# 100x75_BOB.net
KiCad netlist of a schematic drawn in EAGLE
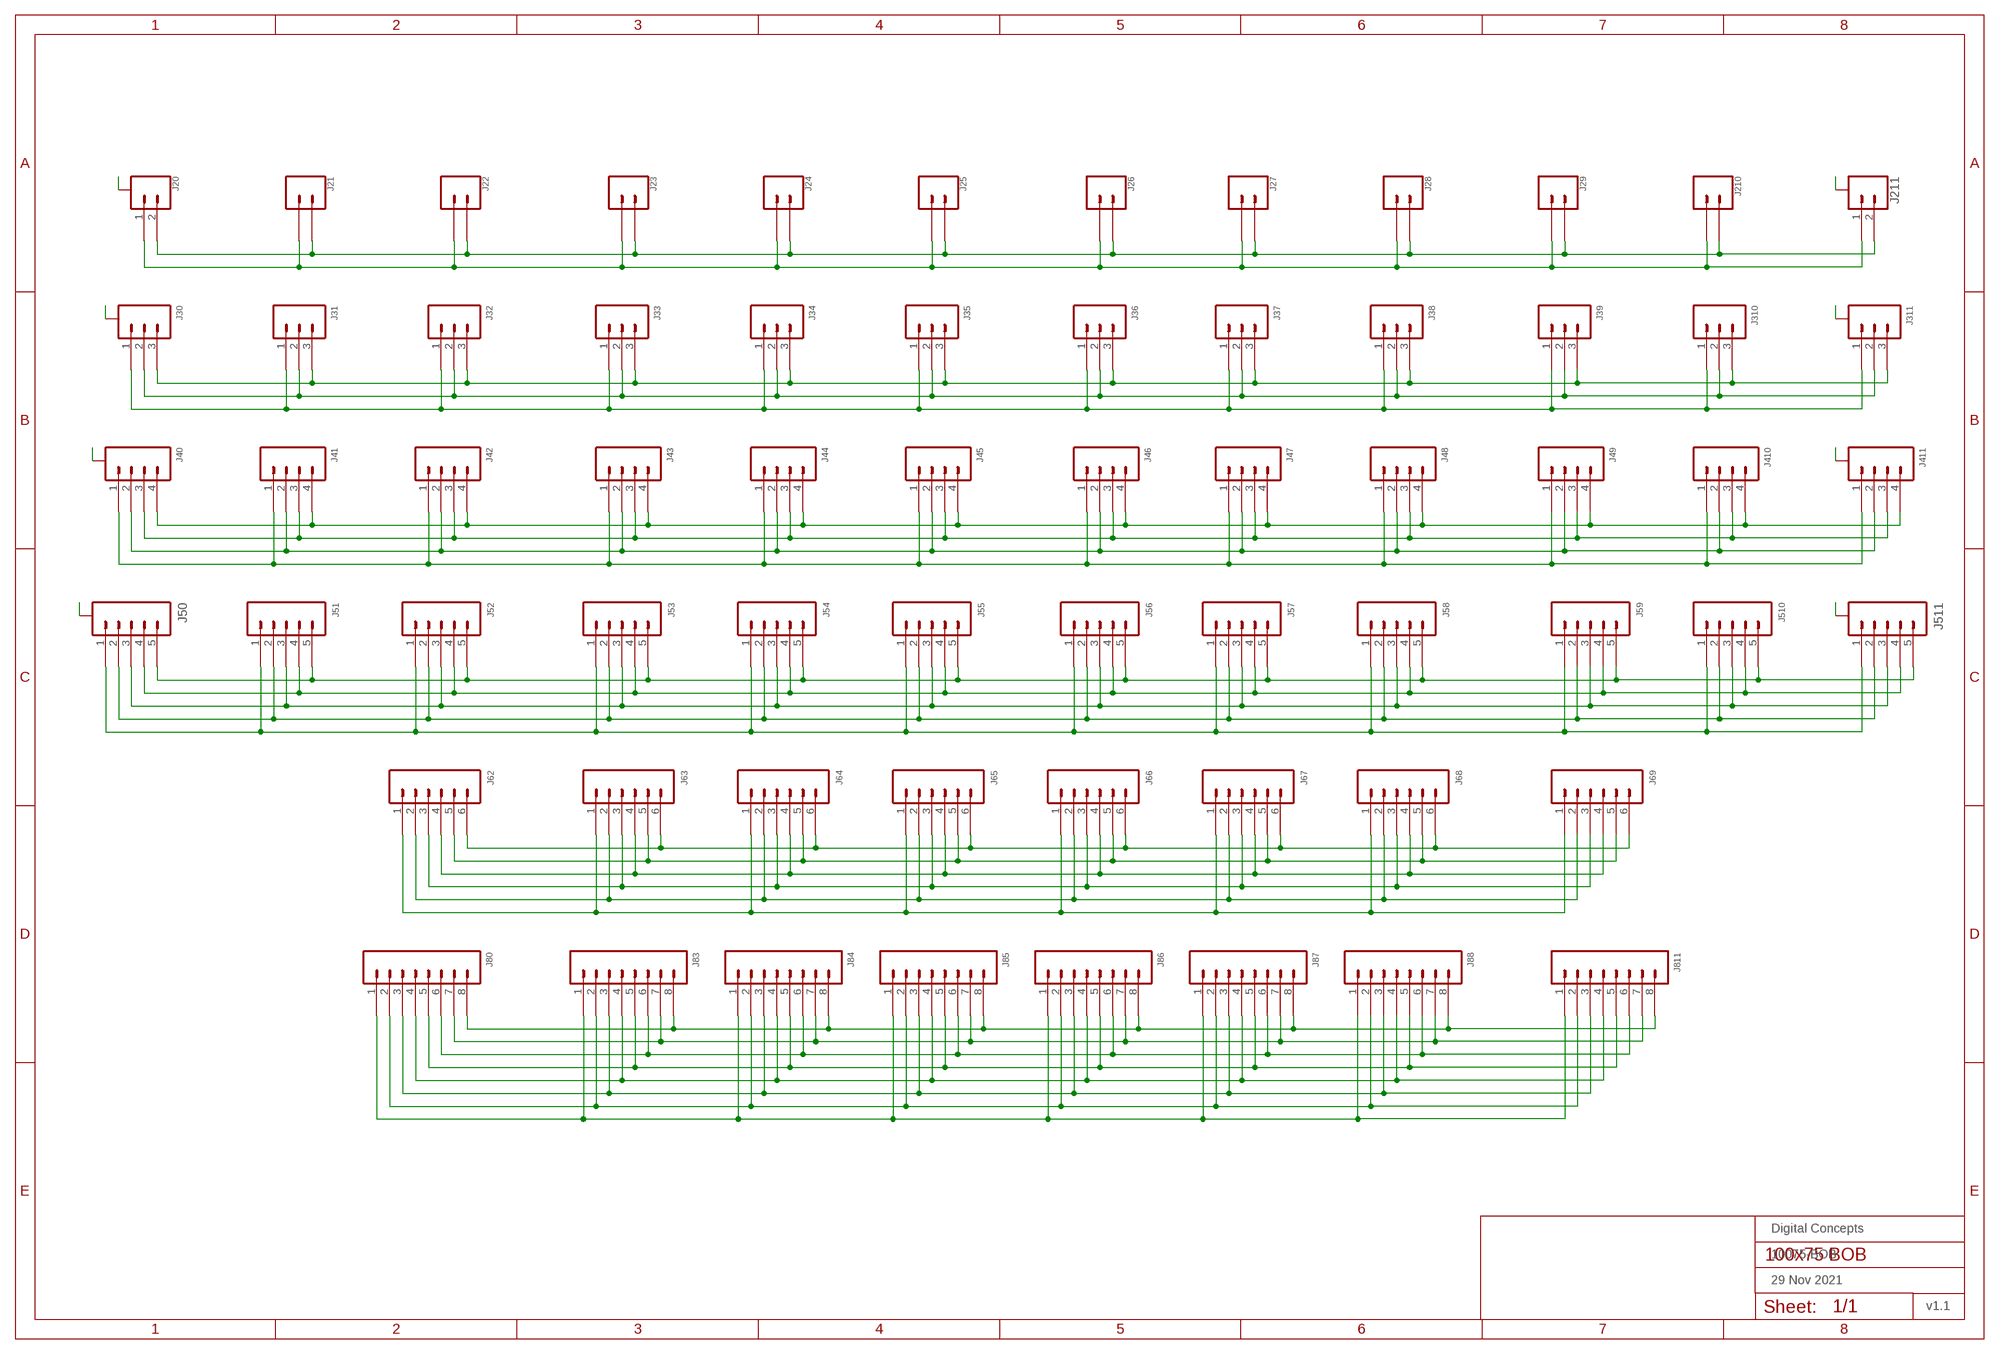
[diagram p0: schematic, sheet 1]

(export (version "E")
  (design (tool "Eeschema 10.0.6"))
  (components
    (comp (ref "J20")
      (value "JST-SH1.0-2-SMD-VERTICAL")
      (footprint "eagle-import:JST-SH1.0-2-VERTICAL")
      (libsource (lib "eagle-import") (part "JST-SH1.0-2-SMD-VERTICAL"))
    )
    (comp (ref "J21")
      (value "JST-GH1.25-2-VERTICAL")
      (footprint "eagle-import:JST-GH1.25-2-VERTICAL")
      (libsource (lib "eagle-import") (part "JST-GH1.25-2-VERTICAL"))
    )
    (comp (ref "J22")
      (value "JST-PH2.0-2-VERTICAL")
      (footprint "eagle-import:JST-PH2.0-2-VERTICAL")
      (libsource (lib "eagle-import") (part "JST-PH2.0-2-VERTICAL"))
    )
    (comp (ref "J23")
      (value "HEADER-1X2-GENERIC")
      (footprint "eagle-import:CONN_02-GENERIC")
      (libsource (lib "eagle-import") (part "HEADER-1X2-GENERIC"))
    )
    (comp (ref "J24")
      (value "HEADER-1X2-GENERIC")
      (footprint "eagle-import:CONN_02-GENERIC")
      (libsource (lib "eagle-import") (part "HEADER-1X2-GENERIC"))
    )
    (comp (ref "J25")
      (value "HEADER-1X2-GENERIC")
      (footprint "eagle-import:CONN_02-GENERIC")
      (libsource (lib "eagle-import") (part "HEADER-1X2-GENERIC"))
    )
    (comp (ref "J26")
      (value "HEADER-1X2-GENERIC")
      (footprint "eagle-import:CONN_02-GENERIC")
      (libsource (lib "eagle-import") (part "HEADER-1X2-GENERIC"))
    )
    (comp (ref "J27")
      (value "HEADER-1X2-GENERIC")
      (footprint "eagle-import:CONN_02-GENERIC")
      (libsource (lib "eagle-import") (part "HEADER-1X2-GENERIC"))
    )
    (comp (ref "J28")
      (value "HEADER-1X2-GENERIC")
      (footprint "eagle-import:CONN_02-GENERIC")
      (libsource (lib "eagle-import") (part "HEADER-1X2-GENERIC"))
    )
    (comp (ref "J29")
      (value "JST-PH2.0-2-VERTICAL")
      (footprint "eagle-import:JST-PH2.0-2-VERTICAL")
      (libsource (lib "eagle-import") (part "JST-PH2.0-2-VERTICAL"))
    )
    (comp (ref "J30")
      (value "JST-SH1.0-3-SMD-VERTICAL")
      (footprint "eagle-import:JST-SH1.0-3-VERTICAL")
      (libsource (lib "eagle-import") (part "JST-SH1.0-3-SMD-VERTICAL"))
    )
    (comp (ref "J31")
      (value "JST-GH1.25-3-VERTICAL")
      (footprint "eagle-import:JST-GH1.25-3-VERTICAL")
      (libsource (lib "eagle-import") (part "JST-GH1.25-3-VERTICAL"))
    )
    (comp (ref "J32")
      (value "JST-PH2.0-3-VERTICAL")
      (footprint "eagle-import:JST-PH2.0-3-VERTICAL")
      (libsource (lib "eagle-import") (part "JST-PH2.0-3-VERTICAL"))
    )
    (comp (ref "J33")
      (value "HEADER-1X3-GENERIC")
      (footprint "eagle-import:CONN_03-GENERIC")
      (libsource (lib "eagle-import") (part "HEADER-1X3-GENERIC"))
    )
    (comp (ref "J34")
      (value "HEADER-1X3-GENERIC")
      (footprint "eagle-import:CONN_03-GENERIC")
      (libsource (lib "eagle-import") (part "HEADER-1X3-GENERIC"))
    )
    (comp (ref "J35")
      (value "HEADER-1X3-GENERIC")
      (footprint "eagle-import:CONN_03-GENERIC")
      (libsource (lib "eagle-import") (part "HEADER-1X3-GENERIC"))
    )
    (comp (ref "J36")
      (value "HEADER-1X3-GENERIC")
      (footprint "eagle-import:CONN_03-GENERIC")
      (libsource (lib "eagle-import") (part "HEADER-1X3-GENERIC"))
    )
    (comp (ref "J37")
      (value "HEADER-1X3-GENERIC")
      (footprint "eagle-import:CONN_03-GENERIC")
      (libsource (lib "eagle-import") (part "HEADER-1X3-GENERIC"))
    )
    (comp (ref "J38")
      (value "HEADER-1X3-GENERIC")
      (footprint "eagle-import:CONN_03-GENERIC")
      (libsource (lib "eagle-import") (part "HEADER-1X3-GENERIC"))
    )
    (comp (ref "J39")
      (value "JST-PH2.0-3-VERTICAL")
      (footprint "eagle-import:JST-PH2.0-3-VERTICAL")
      (libsource (lib "eagle-import") (part "JST-PH2.0-3-VERTICAL"))
    )
    (comp (ref "J40")
      (value "JST-SH1.0-4-SMD-VERTICAL")
      (footprint "eagle-import:JST-SH1.0-4-VERTICAL")
      (libsource (lib "eagle-import") (part "JST-SH1.0-4-SMD-VERTICAL"))
    )
    (comp (ref "J41")
      (value "JST-GH1.25-4-VERTICAL")
      (footprint "eagle-import:JST-GH1.25-4-VERTICAL")
      (libsource (lib "eagle-import") (part "JST-GH1.25-4-VERTICAL"))
    )
    (comp (ref "J42")
      (value "JST-PH2.0-4-VERTICAL")
      (footprint "eagle-import:JST-PH2.0-4-VERTICAL")
      (libsource (lib "eagle-import") (part "JST-PH2.0-4-VERTICAL"))
    )
    (comp (ref "J43")
      (value "HEADER-1X4-GENERIC")
      (footprint "eagle-import:CONN_04-GENERIC")
      (libsource (lib "eagle-import") (part "HEADER-1X4-GENERIC"))
    )
    (comp (ref "J44")
      (value "HEADER-1X4-GENERIC")
      (footprint "eagle-import:CONN_04-GENERIC")
      (libsource (lib "eagle-import") (part "HEADER-1X4-GENERIC"))
    )
    (comp (ref "J45")
      (value "HEADER-1X4-GENERIC")
      (footprint "eagle-import:CONN_04-GENERIC")
      (libsource (lib "eagle-import") (part "HEADER-1X4-GENERIC"))
    )
    (comp (ref "J46")
      (value "HEADER-1X4-GENERIC")
      (footprint "eagle-import:CONN_04-GENERIC")
      (libsource (lib "eagle-import") (part "HEADER-1X4-GENERIC"))
    )
    (comp (ref "J47")
      (value "HEADER-1X4-GENERIC")
      (footprint "eagle-import:CONN_04-GENERIC")
      (libsource (lib "eagle-import") (part "HEADER-1X4-GENERIC"))
    )
    (comp (ref "J48")
      (value "HEADER-1X4-GENERIC")
      (footprint "eagle-import:CONN_04-GENERIC")
      (libsource (lib "eagle-import") (part "HEADER-1X4-GENERIC"))
    )
    (comp (ref "J49")
      (value "JST-PH2.0-4-VERTICAL")
      (footprint "eagle-import:JST-PH2.0-4-VERTICAL")
      (libsource (lib "eagle-import") (part "JST-PH2.0-4-VERTICAL"))
    )
    (comp (ref "J50")
      (value "JST-SH1.0-5-SMD-VERTICAL")
      (footprint "eagle-import:JST-SH1.0-5-VERTICAL")
      (libsource (lib "eagle-import") (part "JST-SH1.0-5-SMD-VERTICAL"))
    )
    (comp (ref "J51")
      (value "JST-GH1.25-5-VERTICAL")
      (footprint "eagle-import:JST-GH1.25-5-VERTICAL")
      (libsource (lib "eagle-import") (part "JST-GH1.25-5-VERTICAL"))
    )
    (comp (ref "J52")
      (value "JST-PH2.0-5-VERTICAL")
      (footprint "eagle-import:JST-PH2.0-5-VERTICAL")
      (libsource (lib "eagle-import") (part "JST-PH2.0-5-VERTICAL"))
    )
    (comp (ref "J53")
      (value "HEADER-1X5-GENERIC")
      (footprint "eagle-import:CONN_05-GENERIC")
      (libsource (lib "eagle-import") (part "HEADER-1X5-GENERIC"))
    )
    (comp (ref "J54")
      (value "HEADER-1X5-GENERIC")
      (footprint "eagle-import:CONN_05-GENERIC")
      (libsource (lib "eagle-import") (part "HEADER-1X5-GENERIC"))
    )
    (comp (ref "J55")
      (value "HEADER-1X5-GENERIC")
      (footprint "eagle-import:CONN_05-GENERIC")
      (libsource (lib "eagle-import") (part "HEADER-1X5-GENERIC"))
    )
    (comp (ref "J56")
      (value "HEADER-1X5-GENERIC")
      (footprint "eagle-import:CONN_05-GENERIC")
      (libsource (lib "eagle-import") (part "HEADER-1X5-GENERIC"))
    )
    (comp (ref "J57")
      (value "HEADER-1X5-GENERIC")
      (footprint "eagle-import:CONN_05-GENERIC")
      (libsource (lib "eagle-import") (part "HEADER-1X5-GENERIC"))
    )
    (comp (ref "J58")
      (value "HEADER-1X5-GENERIC")
      (footprint "eagle-import:CONN_05-GENERIC")
      (libsource (lib "eagle-import") (part "HEADER-1X5-GENERIC"))
    )
    (comp (ref "J59")
      (value "JST-PH2.0-5-VERTICAL")
      (footprint "eagle-import:JST-PH2.0-5-VERTICAL")
      (libsource (lib "eagle-import") (part "JST-PH2.0-5-VERTICAL"))
    )
    (comp (ref "J62")
      (value "RJ11-6P6C-VERTICAL")
      (footprint "eagle-import:RJ11-6-VERTICAL")
      (libsource (lib "eagle-import") (part "RJ11-6P6C-VERTICAL"))
    )
    (comp (ref "J63")
      (value "HEADER-1X6-GENERIC")
      (footprint "eagle-import:CONN_06-GENERIC")
      (libsource (lib "eagle-import") (part "HEADER-1X6-GENERIC"))
    )
    (comp (ref "J64")
      (value "HEADER-1X6-GENERIC")
      (footprint "eagle-import:CONN_06-GENERIC")
      (libsource (lib "eagle-import") (part "HEADER-1X6-GENERIC"))
    )
    (comp (ref "J65")
      (value "HEADER-1X6-GENERIC")
      (footprint "eagle-import:CONN_06-GENERIC")
      (libsource (lib "eagle-import") (part "HEADER-1X6-GENERIC"))
    )
    (comp (ref "J66")
      (value "HEADER-1X6-GENERIC")
      (footprint "eagle-import:CONN_06-GENERIC")
      (libsource (lib "eagle-import") (part "HEADER-1X6-GENERIC"))
    )
    (comp (ref "J67")
      (value "HEADER-1X6-GENERIC")
      (footprint "eagle-import:CONN_06-GENERIC")
      (libsource (lib "eagle-import") (part "HEADER-1X6-GENERIC"))
    )
    (comp (ref "J68")
      (value "HEADER-1X6-GENERIC")
      (footprint "eagle-import:CONN_06-GENERIC")
      (libsource (lib "eagle-import") (part "HEADER-1X6-GENERIC"))
    )
    (comp (ref "J69")
      (value "RJ11-6P6C-VERTICAL")
      (footprint "eagle-import:RJ11-6-VERTICAL")
      (libsource (lib "eagle-import") (part "RJ11-6P6C-VERTICAL"))
    )
    (comp (ref "J80")
      (value "RJ45-8P8C-VERTICAL-MK2")
      (footprint "eagle-import:RJ45-VERTICAL-MK2")
      (libsource (lib "eagle-import") (part "RJ45-8P8C-VERTICAL-MK2"))
    )
    (comp (ref "J83")
      (value "HEADER-1X8-GENERIC")
      (footprint "eagle-import:CONN_08-GENERIC")
      (libsource (lib "eagle-import") (part "HEADER-1X8-GENERIC"))
    )
    (comp (ref "J84")
      (value "HEADER-1X8-GENERIC")
      (footprint "eagle-import:CONN_08-GENERIC")
      (libsource (lib "eagle-import") (part "HEADER-1X8-GENERIC"))
    )
    (comp (ref "J85")
      (value "HEADER-1X8-GENERIC")
      (footprint "eagle-import:CONN_08-GENERIC")
      (libsource (lib "eagle-import") (part "HEADER-1X8-GENERIC"))
    )
    (comp (ref "J86")
      (value "HEADER-1X8-GENERIC")
      (footprint "eagle-import:CONN_08-GENERIC")
      (libsource (lib "eagle-import") (part "HEADER-1X8-GENERIC"))
    )
    (comp (ref "J87")
      (value "HEADER-1X8-GENERIC")
      (footprint "eagle-import:CONN_08-GENERIC")
      (libsource (lib "eagle-import") (part "HEADER-1X8-GENERIC"))
    )
    (comp (ref "J88")
      (value "HEADER-1X8-GENERIC")
      (footprint "eagle-import:CONN_08-GENERIC")
      (libsource (lib "eagle-import") (part "HEADER-1X8-GENERIC"))
    )
    (comp (ref "J210")
      (value "JST-GH1.25-2-VERTICAL")
      (footprint "eagle-import:JST-GH1.25-2-VERTICAL")
      (libsource (lib "eagle-import") (part "JST-GH1.25-2-VERTICAL"))
    )
    (comp (ref "J211")
      (value "JST-SH1.0-2-SMD-VERTICAL")
      (footprint "eagle-import:JST-SH1.0-2-VERTICAL")
      (libsource (lib "eagle-import") (part "JST-SH1.0-2-SMD-VERTICAL"))
    )
    (comp (ref "J310")
      (value "JST-GH1.25-3-VERTICAL")
      (footprint "eagle-import:JST-GH1.25-3-VERTICAL")
      (libsource (lib "eagle-import") (part "JST-GH1.25-3-VERTICAL"))
    )
    (comp (ref "J311")
      (value "JST-SH1.0-3-SMD-VERTICAL")
      (footprint "eagle-import:JST-SH1.0-3-VERTICAL")
      (libsource (lib "eagle-import") (part "JST-SH1.0-3-SMD-VERTICAL"))
    )
    (comp (ref "J410")
      (value "JST-GH1.25-4-VERTICAL")
      (footprint "eagle-import:JST-GH1.25-4-VERTICAL")
      (libsource (lib "eagle-import") (part "JST-GH1.25-4-VERTICAL"))
    )
    (comp (ref "J411")
      (value "JST-SH1.0-4-SMD-VERTICAL")
      (footprint "eagle-import:JST-SH1.0-4-VERTICAL")
      (libsource (lib "eagle-import") (part "JST-SH1.0-4-SMD-VERTICAL"))
    )
    (comp (ref "J510")
      (value "JST-GH1.25-5-VERTICAL")
      (footprint "eagle-import:JST-GH1.25-5-VERTICAL")
      (libsource (lib "eagle-import") (part "JST-GH1.25-5-VERTICAL"))
    )
    (comp (ref "J511")
      (value "JST-SH1.0-5-SMD-VERTICAL")
      (footprint "eagle-import:JST-SH1.0-5-VERTICAL")
      (libsource (lib "eagle-import") (part "JST-SH1.0-5-SMD-VERTICAL"))
    )
    (comp (ref "J811")
      (value "RJ45-8P8C-VERTICAL-MK2")
      (footprint "eagle-import:RJ45-VERTICAL-MK2")
      (libsource (lib "eagle-import") (part "RJ45-8P8C-VERTICAL-MK2"))
    )
  )
  (nets
    (net (code "1") (name "/A") (class "Default")
      (node (ref "J20") (pin "A@1") (pinfunction "A_A@1") (pintype "power_in"))
      (node (ref "J20") (pin "A@2") (pinfunction "A_A@2") (pintype "power_in"))
      (node (ref "J211") (pin "A@1") (pinfunction "A_A@1") (pintype "power_in"))
      (node (ref "J211") (pin "A@2") (pinfunction "A_A@2") (pintype "power_in"))
      (node (ref "J30") (pin "A@1") (pinfunction "A_A@1") (pintype "power_in"))
      (node (ref "J30") (pin "A@3") (pinfunction "A_A@3") (pintype "power_in"))
      (node (ref "J311") (pin "A@1") (pinfunction "A_A@1") (pintype "power_in"))
      (node (ref "J311") (pin "A@3") (pinfunction "A_A@3") (pintype "power_in"))
      (node (ref "J40") (pin "A@1") (pinfunction "A_A@1") (pintype "power_in"))
      (node (ref "J40") (pin "A@4") (pinfunction "A_A@4") (pintype "power_in"))
      (node (ref "J411") (pin "A@1") (pinfunction "A_A@1") (pintype "power_in"))
      (node (ref "J411") (pin "A@4") (pinfunction "A_A@4") (pintype "power_in"))
      (node (ref "J50") (pin "A@1") (pinfunction "A_A@1") (pintype "power_in"))
      (node (ref "J50") (pin "A@5") (pinfunction "A_A@5") (pintype "power_in"))
      (node (ref "J511") (pin "A@1") (pinfunction "A_A@1") (pintype "power_in"))
      (node (ref "J511") (pin "A@5") (pinfunction "A_A@5") (pintype "power_in"))
    )
    (net (code "2") (name "Net-(J20-Pad1)") (class "Default")
      (node (ref "J20") (pin "1") (pinfunction "1_1") (pintype "passive"))
      (node (ref "J21") (pin "1") (pinfunction "1_1") (pintype "passive"))
      (node (ref "J210") (pin "1") (pinfunction "1_1") (pintype "passive"))
      (node (ref "J211") (pin "1") (pinfunction "1_1") (pintype "passive"))
      (node (ref "J22") (pin "1") (pinfunction "1_1") (pintype "passive"))
      (node (ref "J23") (pin "1") (pinfunction "1_1") (pintype "passive"))
      (node (ref "J24") (pin "1") (pinfunction "1_1") (pintype "passive"))
      (node (ref "J25") (pin "1") (pinfunction "1_1") (pintype "passive"))
      (node (ref "J26") (pin "1") (pinfunction "1_1") (pintype "passive"))
      (node (ref "J27") (pin "1") (pinfunction "1_1") (pintype "passive"))
      (node (ref "J28") (pin "1") (pinfunction "1_1") (pintype "passive"))
      (node (ref "J29") (pin "1") (pinfunction "1_1") (pintype "passive"))
    )
    (net (code "3") (name "Net-(J20-Pad2)") (class "Default")
      (node (ref "J20") (pin "2") (pinfunction "2_2") (pintype "passive"))
      (node (ref "J21") (pin "2") (pinfunction "2_2") (pintype "passive"))
      (node (ref "J210") (pin "2") (pinfunction "2_2") (pintype "passive"))
      (node (ref "J211") (pin "2") (pinfunction "2_2") (pintype "passive"))
      (node (ref "J22") (pin "2") (pinfunction "2_2") (pintype "passive"))
      (node (ref "J23") (pin "2") (pinfunction "2_2") (pintype "passive"))
      (node (ref "J24") (pin "2") (pinfunction "2_2") (pintype "passive"))
      (node (ref "J25") (pin "2") (pinfunction "2_2") (pintype "passive"))
      (node (ref "J26") (pin "2") (pinfunction "2_2") (pintype "passive"))
      (node (ref "J27") (pin "2") (pinfunction "2_2") (pintype "passive"))
      (node (ref "J28") (pin "2") (pinfunction "2_2") (pintype "passive"))
      (node (ref "J29") (pin "2") (pinfunction "2_2") (pintype "passive"))
    )
    (net (code "4") (name "Net-(J30-Pad1)") (class "Default")
      (node (ref "J30") (pin "1") (pinfunction "1_1") (pintype "passive"))
      (node (ref "J31") (pin "1") (pinfunction "1_1") (pintype "passive"))
      (node (ref "J310") (pin "1") (pinfunction "1_1") (pintype "passive"))
      (node (ref "J311") (pin "1") (pinfunction "1_1") (pintype "passive"))
      (node (ref "J32") (pin "1") (pinfunction "1_1") (pintype "passive"))
      (node (ref "J33") (pin "1") (pinfunction "1_1") (pintype "passive"))
      (node (ref "J34") (pin "1") (pinfunction "1_1") (pintype "passive"))
      (node (ref "J35") (pin "1") (pinfunction "1_1") (pintype "passive"))
      (node (ref "J36") (pin "1") (pinfunction "1_1") (pintype "passive"))
      (node (ref "J37") (pin "1") (pinfunction "1_1") (pintype "passive"))
      (node (ref "J38") (pin "1") (pinfunction "1_1") (pintype "passive"))
      (node (ref "J39") (pin "1") (pinfunction "1_1") (pintype "passive"))
    )
    (net (code "5") (name "Net-(J30-Pad2)") (class "Default")
      (node (ref "J30") (pin "2") (pinfunction "2_2") (pintype "passive"))
      (node (ref "J31") (pin "2") (pinfunction "2_2") (pintype "passive"))
      (node (ref "J310") (pin "2") (pinfunction "2_2") (pintype "passive"))
      (node (ref "J311") (pin "2") (pinfunction "2_2") (pintype "passive"))
      (node (ref "J32") (pin "2") (pinfunction "2_2") (pintype "passive"))
      (node (ref "J33") (pin "2") (pinfunction "2_2") (pintype "passive"))
      (node (ref "J34") (pin "2") (pinfunction "2_2") (pintype "passive"))
      (node (ref "J35") (pin "2") (pinfunction "2_2") (pintype "passive"))
      (node (ref "J36") (pin "2") (pinfunction "2_2") (pintype "passive"))
      (node (ref "J37") (pin "2") (pinfunction "2_2") (pintype "passive"))
      (node (ref "J38") (pin "2") (pinfunction "2_2") (pintype "passive"))
      (node (ref "J39") (pin "2") (pinfunction "2_2") (pintype "passive"))
    )
    (net (code "6") (name "Net-(J30-Pad3)") (class "Default")
      (node (ref "J30") (pin "3") (pinfunction "3_3") (pintype "passive"))
      (node (ref "J31") (pin "3") (pinfunction "3_3") (pintype "passive"))
      (node (ref "J310") (pin "3") (pinfunction "3_3") (pintype "passive"))
      (node (ref "J311") (pin "3") (pinfunction "3_3") (pintype "passive"))
      (node (ref "J32") (pin "3") (pinfunction "3_3") (pintype "passive"))
      (node (ref "J33") (pin "3") (pinfunction "3_3") (pintype "passive"))
      (node (ref "J34") (pin "3") (pinfunction "3_3") (pintype "passive"))
      (node (ref "J35") (pin "3") (pinfunction "3_3") (pintype "passive"))
      (node (ref "J36") (pin "3") (pinfunction "3_3") (pintype "passive"))
      (node (ref "J37") (pin "3") (pinfunction "3_3") (pintype "passive"))
      (node (ref "J38") (pin "3") (pinfunction "3_3") (pintype "passive"))
      (node (ref "J39") (pin "3") (pinfunction "3_3") (pintype "passive"))
    )
    (net (code "7") (name "Net-(J40-Pad1)") (class "Default")
      (node (ref "J40") (pin "1") (pinfunction "1_1") (pintype "passive"))
      (node (ref "J41") (pin "1") (pinfunction "1_1") (pintype "passive"))
      (node (ref "J410") (pin "1") (pinfunction "1_1") (pintype "passive"))
      (node (ref "J411") (pin "1") (pinfunction "1_1") (pintype "passive"))
      (node (ref "J42") (pin "1") (pinfunction "1_1") (pintype "passive"))
      (node (ref "J43") (pin "1") (pinfunction "1_1") (pintype "passive"))
      (node (ref "J44") (pin "1") (pinfunction "1_1") (pintype "passive"))
      (node (ref "J45") (pin "1") (pinfunction "1_1") (pintype "passive"))
      (node (ref "J46") (pin "1") (pinfunction "1_1") (pintype "passive"))
      (node (ref "J47") (pin "1") (pinfunction "1_1") (pintype "passive"))
      (node (ref "J48") (pin "1") (pinfunction "1_1") (pintype "passive"))
      (node (ref "J49") (pin "1") (pinfunction "1_1") (pintype "passive"))
    )
    (net (code "8") (name "Net-(J40-Pad2)") (class "Default")
      (node (ref "J40") (pin "2") (pinfunction "2_2") (pintype "passive"))
      (node (ref "J41") (pin "2") (pinfunction "2_2") (pintype "passive"))
      (node (ref "J410") (pin "2") (pinfunction "2_2") (pintype "passive"))
      (node (ref "J411") (pin "2") (pinfunction "2_2") (pintype "passive"))
      (node (ref "J42") (pin "2") (pinfunction "2_2") (pintype "passive"))
      (node (ref "J43") (pin "2") (pinfunction "2_2") (pintype "passive"))
      (node (ref "J44") (pin "2") (pinfunction "2_2") (pintype "passive"))
      (node (ref "J45") (pin "2") (pinfunction "2_2") (pintype "passive"))
      (node (ref "J46") (pin "2") (pinfunction "2_2") (pintype "passive"))
      (node (ref "J47") (pin "2") (pinfunction "2_2") (pintype "passive"))
      (node (ref "J48") (pin "2") (pinfunction "2_2") (pintype "passive"))
      (node (ref "J49") (pin "2") (pinfunction "2_2") (pintype "passive"))
    )
    (net (code "9") (name "Net-(J40-Pad3)") (class "Default")
      (node (ref "J40") (pin "3") (pinfunction "3_3") (pintype "passive"))
      (node (ref "J41") (pin "3") (pinfunction "3_3") (pintype "passive"))
      (node (ref "J410") (pin "3") (pinfunction "3_3") (pintype "passive"))
      (node (ref "J411") (pin "3") (pinfunction "3_3") (pintype "passive"))
      (node (ref "J42") (pin "3") (pinfunction "3_3") (pintype "passive"))
      (node (ref "J43") (pin "3") (pinfunction "3_3") (pintype "passive"))
      (node (ref "J44") (pin "3") (pinfunction "3_3") (pintype "passive"))
      (node (ref "J45") (pin "3") (pinfunction "3_3") (pintype "passive"))
      (node (ref "J46") (pin "3") (pinfunction "3_3") (pintype "passive"))
      (node (ref "J47") (pin "3") (pinfunction "3_3") (pintype "passive"))
      (node (ref "J48") (pin "3") (pinfunction "3_3") (pintype "passive"))
      (node (ref "J49") (pin "3") (pinfunction "3_3") (pintype "passive"))
    )
    (net (code "10") (name "Net-(J40-Pad4)") (class "Default")
      (node (ref "J40") (pin "4") (pinfunction "4_4") (pintype "passive"))
      (node (ref "J41") (pin "4") (pinfunction "4_4") (pintype "passive"))
      (node (ref "J410") (pin "4") (pinfunction "4_4") (pintype "passive"))
      (node (ref "J411") (pin "4") (pinfunction "4_4") (pintype "passive"))
      (node (ref "J42") (pin "4") (pinfunction "4_4") (pintype "passive"))
      (node (ref "J43") (pin "4") (pinfunction "4_4") (pintype "passive"))
      (node (ref "J44") (pin "4") (pinfunction "4_4") (pintype "passive"))
      (node (ref "J45") (pin "4") (pinfunction "4_4") (pintype "passive"))
      (node (ref "J46") (pin "4") (pinfunction "4_4") (pintype "passive"))
      (node (ref "J47") (pin "4") (pinfunction "4_4") (pintype "passive"))
      (node (ref "J48") (pin "4") (pinfunction "4_4") (pintype "passive"))
      (node (ref "J49") (pin "4") (pinfunction "4_4") (pintype "passive"))
    )
    (net (code "11") (name "Net-(J50-Pad1)") (class "Default")
      (node (ref "J50") (pin "1") (pinfunction "1_1") (pintype "passive"))
      (node (ref "J51") (pin "1") (pinfunction "1_1") (pintype "passive"))
      (node (ref "J510") (pin "1") (pinfunction "1_1") (pintype "passive"))
      (node (ref "J511") (pin "1") (pinfunction "1_1") (pintype "passive"))
      (node (ref "J52") (pin "1") (pinfunction "1_1") (pintype "passive"))
      (node (ref "J53") (pin "1") (pinfunction "1_1") (pintype "passive"))
      (node (ref "J54") (pin "1") (pinfunction "1_1") (pintype "passive"))
      (node (ref "J55") (pin "1") (pinfunction "1_1") (pintype "passive"))
      (node (ref "J56") (pin "1") (pinfunction "1_1") (pintype "passive"))
      (node (ref "J57") (pin "1") (pinfunction "1_1") (pintype "passive"))
      (node (ref "J58") (pin "1") (pinfunction "1_1") (pintype "passive"))
      (node (ref "J59") (pin "1") (pinfunction "1_1") (pintype "passive"))
    )
    (net (code "12") (name "Net-(J50-Pad2)") (class "Default")
      (node (ref "J50") (pin "2") (pinfunction "2_2") (pintype "passive"))
      (node (ref "J51") (pin "2") (pinfunction "2_2") (pintype "passive"))
      (node (ref "J510") (pin "2") (pinfunction "2_2") (pintype "passive"))
      (node (ref "J511") (pin "2") (pinfunction "2_2") (pintype "passive"))
      (node (ref "J52") (pin "2") (pinfunction "2_2") (pintype "passive"))
      (node (ref "J53") (pin "2") (pinfunction "2_2") (pintype "passive"))
      (node (ref "J54") (pin "2") (pinfunction "2_2") (pintype "passive"))
      (node (ref "J55") (pin "2") (pinfunction "2_2") (pintype "passive"))
      (node (ref "J56") (pin "2") (pinfunction "2_2") (pintype "passive"))
      (node (ref "J57") (pin "2") (pinfunction "2_2") (pintype "passive"))
      (node (ref "J58") (pin "2") (pinfunction "2_2") (pintype "passive"))
      (node (ref "J59") (pin "2") (pinfunction "2_2") (pintype "passive"))
    )
    (net (code "13") (name "Net-(J50-Pad3)") (class "Default")
      (node (ref "J50") (pin "3") (pinfunction "3_3") (pintype "passive"))
      (node (ref "J51") (pin "3") (pinfunction "3_3") (pintype "passive"))
      (node (ref "J510") (pin "3") (pinfunction "3_3") (pintype "passive"))
      (node (ref "J511") (pin "3") (pinfunction "3_3") (pintype "passive"))
      (node (ref "J52") (pin "3") (pinfunction "3_3") (pintype "passive"))
      (node (ref "J53") (pin "3") (pinfunction "3_3") (pintype "passive"))
      (node (ref "J54") (pin "3") (pinfunction "3_3") (pintype "passive"))
      (node (ref "J55") (pin "3") (pinfunction "3_3") (pintype "passive"))
      (node (ref "J56") (pin "3") (pinfunction "3_3") (pintype "passive"))
      (node (ref "J57") (pin "3") (pinfunction "3_3") (pintype "passive"))
      (node (ref "J58") (pin "3") (pinfunction "3_3") (pintype "passive"))
      (node (ref "J59") (pin "3") (pinfunction "3_3") (pintype "passive"))
    )
    (net (code "14") (name "Net-(J50-Pad4)") (class "Default")
      (node (ref "J50") (pin "4") (pinfunction "4_4") (pintype "passive"))
      (node (ref "J51") (pin "4") (pinfunction "4_4") (pintype "passive"))
      (node (ref "J510") (pin "4") (pinfunction "4_4") (pintype "passive"))
      (node (ref "J511") (pin "4") (pinfunction "4_4") (pintype "passive"))
      (node (ref "J52") (pin "4") (pinfunction "4_4") (pintype "passive"))
      (node (ref "J53") (pin "4") (pinfunction "4_4") (pintype "passive"))
      (node (ref "J54") (pin "4") (pinfunction "4_4") (pintype "passive"))
      (node (ref "J55") (pin "4") (pinfunction "4_4") (pintype "passive"))
      (node (ref "J56") (pin "4") (pinfunction "4_4") (pintype "passive"))
      (node (ref "J57") (pin "4") (pinfunction "4_4") (pintype "passive"))
      (node (ref "J58") (pin "4") (pinfunction "4_4") (pintype "passive"))
      (node (ref "J59") (pin "4") (pinfunction "4_4") (pintype "passive"))
    )
    (net (code "15") (name "Net-(J50-Pad5)") (class "Default")
      (node (ref "J50") (pin "5") (pinfunction "5_5") (pintype "passive"))
      (node (ref "J51") (pin "5") (pinfunction "5_5") (pintype "passive"))
      (node (ref "J510") (pin "5") (pinfunction "5_5") (pintype "passive"))
      (node (ref "J511") (pin "5") (pinfunction "5_5") (pintype "passive"))
      (node (ref "J52") (pin "5") (pinfunction "5_5") (pintype "passive"))
      (node (ref "J53") (pin "5") (pinfunction "5_5") (pintype "passive"))
      (node (ref "J54") (pin "5") (pinfunction "5_5") (pintype "passive"))
      (node (ref "J55") (pin "5") (pinfunction "5_5") (pintype "passive"))
      (node (ref "J56") (pin "5") (pinfunction "5_5") (pintype "passive"))
      (node (ref "J57") (pin "5") (pinfunction "5_5") (pintype "passive"))
      (node (ref "J58") (pin "5") (pinfunction "5_5") (pintype "passive"))
      (node (ref "J59") (pin "5") (pinfunction "5_5") (pintype "passive"))
    )
    (net (code "16") (name "Net-(J62-Pad1)") (class "Default")
      (node (ref "J62") (pin "1") (pinfunction "1_1") (pintype "passive"))
      (node (ref "J63") (pin "1") (pinfunction "1_1") (pintype "passive"))
      (node (ref "J64") (pin "1") (pinfunction "1_1") (pintype "passive"))
      (node (ref "J65") (pin "1") (pinfunction "1_1") (pintype "passive"))
      (node (ref "J66") (pin "1") (pinfunction "1_1") (pintype "passive"))
      (node (ref "J67") (pin "1") (pinfunction "1_1") (pintype "passive"))
      (node (ref "J68") (pin "1") (pinfunction "1_1") (pintype "passive"))
      (node (ref "J69") (pin "1") (pinfunction "1_1") (pintype "passive"))
    )
    (net (code "17") (name "Net-(J62-Pad2)") (class "Default")
      (node (ref "J62") (pin "2") (pinfunction "2_2") (pintype "passive"))
      (node (ref "J63") (pin "2") (pinfunction "2_2") (pintype "passive"))
      (node (ref "J64") (pin "2") (pinfunction "2_2") (pintype "passive"))
      (node (ref "J65") (pin "2") (pinfunction "2_2") (pintype "passive"))
      (node (ref "J66") (pin "2") (pinfunction "2_2") (pintype "passive"))
      (node (ref "J67") (pin "2") (pinfunction "2_2") (pintype "passive"))
      (node (ref "J68") (pin "2") (pinfunction "2_2") (pintype "passive"))
      (node (ref "J69") (pin "2") (pinfunction "2_2") (pintype "passive"))
    )
    (net (code "18") (name "Net-(J62-Pad3)") (class "Default")
      (node (ref "J62") (pin "3") (pinfunction "3_3") (pintype "passive"))
      (node (ref "J63") (pin "3") (pinfunction "3_3") (pintype "passive"))
      (node (ref "J64") (pin "3") (pinfunction "3_3") (pintype "passive"))
      (node (ref "J65") (pin "3") (pinfunction "3_3") (pintype "passive"))
      (node (ref "J66") (pin "3") (pinfunction "3_3") (pintype "passive"))
      (node (ref "J67") (pin "3") (pinfunction "3_3") (pintype "passive"))
      (node (ref "J68") (pin "3") (pinfunction "3_3") (pintype "passive"))
      (node (ref "J69") (pin "3") (pinfunction "3_3") (pintype "passive"))
    )
    (net (code "19") (name "Net-(J62-Pad4)") (class "Default")
      (node (ref "J62") (pin "4") (pinfunction "4_4") (pintype "passive"))
      (node (ref "J63") (pin "4") (pinfunction "4_4") (pintype "passive"))
      (node (ref "J64") (pin "4") (pinfunction "4_4") (pintype "passive"))
      (node (ref "J65") (pin "4") (pinfunction "4_4") (pintype "passive"))
      (node (ref "J66") (pin "4") (pinfunction "4_4") (pintype "passive"))
      (node (ref "J67") (pin "4") (pinfunction "4_4") (pintype "passive"))
      (node (ref "J68") (pin "4") (pinfunction "4_4") (pintype "passive"))
      (node (ref "J69") (pin "4") (pinfunction "4_4") (pintype "passive"))
    )
    (net (code "20") (name "Net-(J62-Pad5)") (class "Default")
      (node (ref "J62") (pin "5") (pinfunction "5_5") (pintype "passive"))
      (node (ref "J63") (pin "5") (pinfunction "5_5") (pintype "passive"))
      (node (ref "J64") (pin "5") (pinfunction "5_5") (pintype "passive"))
      (node (ref "J65") (pin "5") (pinfunction "5_5") (pintype "passive"))
      (node (ref "J66") (pin "5") (pinfunction "5_5") (pintype "passive"))
      (node (ref "J67") (pin "5") (pinfunction "5_5") (pintype "passive"))
      (node (ref "J68") (pin "5") (pinfunction "5_5") (pintype "passive"))
      (node (ref "J69") (pin "5") (pinfunction "5_5") (pintype "passive"))
    )
    (net (code "21") (name "Net-(J62-Pad6)") (class "Default")
      (node (ref "J62") (pin "6") (pinfunction "6_6") (pintype "passive"))
      (node (ref "J63") (pin "6") (pinfunction "6_6") (pintype "passive"))
      (node (ref "J64") (pin "6") (pinfunction "6_6") (pintype "passive"))
      (node (ref "J65") (pin "6") (pinfunction "6_6") (pintype "passive"))
      (node (ref "J66") (pin "6") (pinfunction "6_6") (pintype "passive"))
      (node (ref "J67") (pin "6") (pinfunction "6_6") (pintype "passive"))
      (node (ref "J68") (pin "6") (pinfunction "6_6") (pintype "passive"))
      (node (ref "J69") (pin "6") (pinfunction "6_6") (pintype "passive"))
    )
    (net (code "22") (name "Net-(J80-Pad1)") (class "Default")
      (node (ref "J80") (pin "1") (pinfunction "1_1") (pintype "passive"))
      (node (ref "J811") (pin "1") (pinfunction "1_1") (pintype "passive"))
      (node (ref "J83") (pin "1") (pinfunction "1_1") (pintype "passive"))
      (node (ref "J84") (pin "1") (pinfunction "1_1") (pintype "passive"))
      (node (ref "J85") (pin "1") (pinfunction "1_1") (pintype "passive"))
      (node (ref "J86") (pin "1") (pinfunction "1_1") (pintype "passive"))
      (node (ref "J87") (pin "1") (pinfunction "1_1") (pintype "passive"))
      (node (ref "J88") (pin "1") (pinfunction "1_1") (pintype "passive"))
    )
    (net (code "23") (name "Net-(J80-Pad2)") (class "Default")
      (node (ref "J80") (pin "2") (pinfunction "2_2") (pintype "passive"))
      (node (ref "J811") (pin "2") (pinfunction "2_2") (pintype "passive"))
      (node (ref "J83") (pin "2") (pinfunction "2_2") (pintype "passive"))
      (node (ref "J84") (pin "2") (pinfunction "2_2") (pintype "passive"))
      (node (ref "J85") (pin "2") (pinfunction "2_2") (pintype "passive"))
      (node (ref "J86") (pin "2") (pinfunction "2_2") (pintype "passive"))
      (node (ref "J87") (pin "2") (pinfunction "2_2") (pintype "passive"))
      (node (ref "J88") (pin "2") (pinfunction "2_2") (pintype "passive"))
    )
    (net (code "24") (name "Net-(J80-Pad3)") (class "Default")
      (node (ref "J80") (pin "3") (pinfunction "3_3") (pintype "passive"))
      (node (ref "J811") (pin "3") (pinfunction "3_3") (pintype "passive"))
      (node (ref "J83") (pin "3") (pinfunction "3_3") (pintype "passive"))
      (node (ref "J84") (pin "3") (pinfunction "3_3") (pintype "passive"))
      (node (ref "J85") (pin "3") (pinfunction "3_3") (pintype "passive"))
      (node (ref "J86") (pin "3") (pinfunction "3_3") (pintype "passive"))
      (node (ref "J87") (pin "3") (pinfunction "3_3") (pintype "passive"))
      (node (ref "J88") (pin "3") (pinfunction "3_3") (pintype "passive"))
    )
    (net (code "25") (name "Net-(J80-Pad4)") (class "Default")
      (node (ref "J80") (pin "4") (pinfunction "4_4") (pintype "passive"))
      (node (ref "J811") (pin "4") (pinfunction "4_4") (pintype "passive"))
      (node (ref "J83") (pin "4") (pinfunction "4_4") (pintype "passive"))
      (node (ref "J84") (pin "4") (pinfunction "4_4") (pintype "passive"))
      (node (ref "J85") (pin "4") (pinfunction "4_4") (pintype "passive"))
      (node (ref "J86") (pin "4") (pinfunction "4_4") (pintype "passive"))
      (node (ref "J87") (pin "4") (pinfunction "4_4") (pintype "passive"))
      (node (ref "J88") (pin "4") (pinfunction "4_4") (pintype "passive"))
    )
    (net (code "26") (name "Net-(J80-Pad5)") (class "Default")
      (node (ref "J80") (pin "5") (pinfunction "5_5") (pintype "passive"))
      (node (ref "J811") (pin "5") (pinfunction "5_5") (pintype "passive"))
      (node (ref "J83") (pin "5") (pinfunction "5_5") (pintype "passive"))
      (node (ref "J84") (pin "5") (pinfunction "5_5") (pintype "passive"))
      (node (ref "J85") (pin "5") (pinfunction "5_5") (pintype "passive"))
      (node (ref "J86") (pin "5") (pinfunction "5_5") (pintype "passive"))
      (node (ref "J87") (pin "5") (pinfunction "5_5") (pintype "passive"))
      (node (ref "J88") (pin "5") (pinfunction "5_5") (pintype "passive"))
    )
    (net (code "27") (name "Net-(J80-Pad6)") (class "Default")
      (node (ref "J80") (pin "6") (pinfunction "6_6") (pintype "passive"))
      (node (ref "J811") (pin "6") (pinfunction "6_6") (pintype "passive"))
      (node (ref "J83") (pin "6") (pinfunction "6_6") (pintype "passive"))
      (node (ref "J84") (pin "6") (pinfunction "6_6") (pintype "passive"))
      (node (ref "J85") (pin "6") (pinfunction "6_6") (pintype "passive"))
      (node (ref "J86") (pin "6") (pinfunction "6_6") (pintype "passive"))
      (node (ref "J87") (pin "6") (pinfunction "6_6") (pintype "passive"))
      (node (ref "J88") (pin "6") (pinfunction "6_6") (pintype "passive"))
    )
    (net (code "28") (name "Net-(J80-Pad7)") (class "Default")
      (node (ref "J80") (pin "7") (pinfunction "7_7") (pintype "passive"))
      (node (ref "J811") (pin "7") (pinfunction "7_7") (pintype "passive"))
      (node (ref "J83") (pin "7") (pinfunction "7_7") (pintype "passive"))
      (node (ref "J84") (pin "7") (pinfunction "7_7") (pintype "passive"))
      (node (ref "J85") (pin "7") (pinfunction "7_7") (pintype "passive"))
      (node (ref "J86") (pin "7") (pinfunction "7_7") (pintype "passive"))
      (node (ref "J87") (pin "7") (pinfunction "7_7") (pintype "passive"))
      (node (ref "J88") (pin "7") (pinfunction "7_7") (pintype "passive"))
    )
    (net (code "29") (name "Net-(J80-Pad8)") (class "Default")
      (node (ref "J80") (pin "8") (pinfunction "8_8") (pintype "passive"))
      (node (ref "J811") (pin "8") (pinfunction "8_8") (pintype "passive"))
      (node (ref "J83") (pin "8") (pinfunction "8_8") (pintype "passive"))
      (node (ref "J84") (pin "8") (pinfunction "8_8") (pintype "passive"))
      (node (ref "J85") (pin "8") (pinfunction "8_8") (pintype "passive"))
      (node (ref "J86") (pin "8") (pinfunction "8_8") (pintype "passive"))
      (node (ref "J87") (pin "8") (pinfunction "8_8") (pintype "passive"))
      (node (ref "J88") (pin "8") (pinfunction "8_8") (pintype "passive"))
    )
  )
)
